# SCH_Keyboard_2024-06-21.net
KiCad netlist of a schematic drawn in EasyEDA
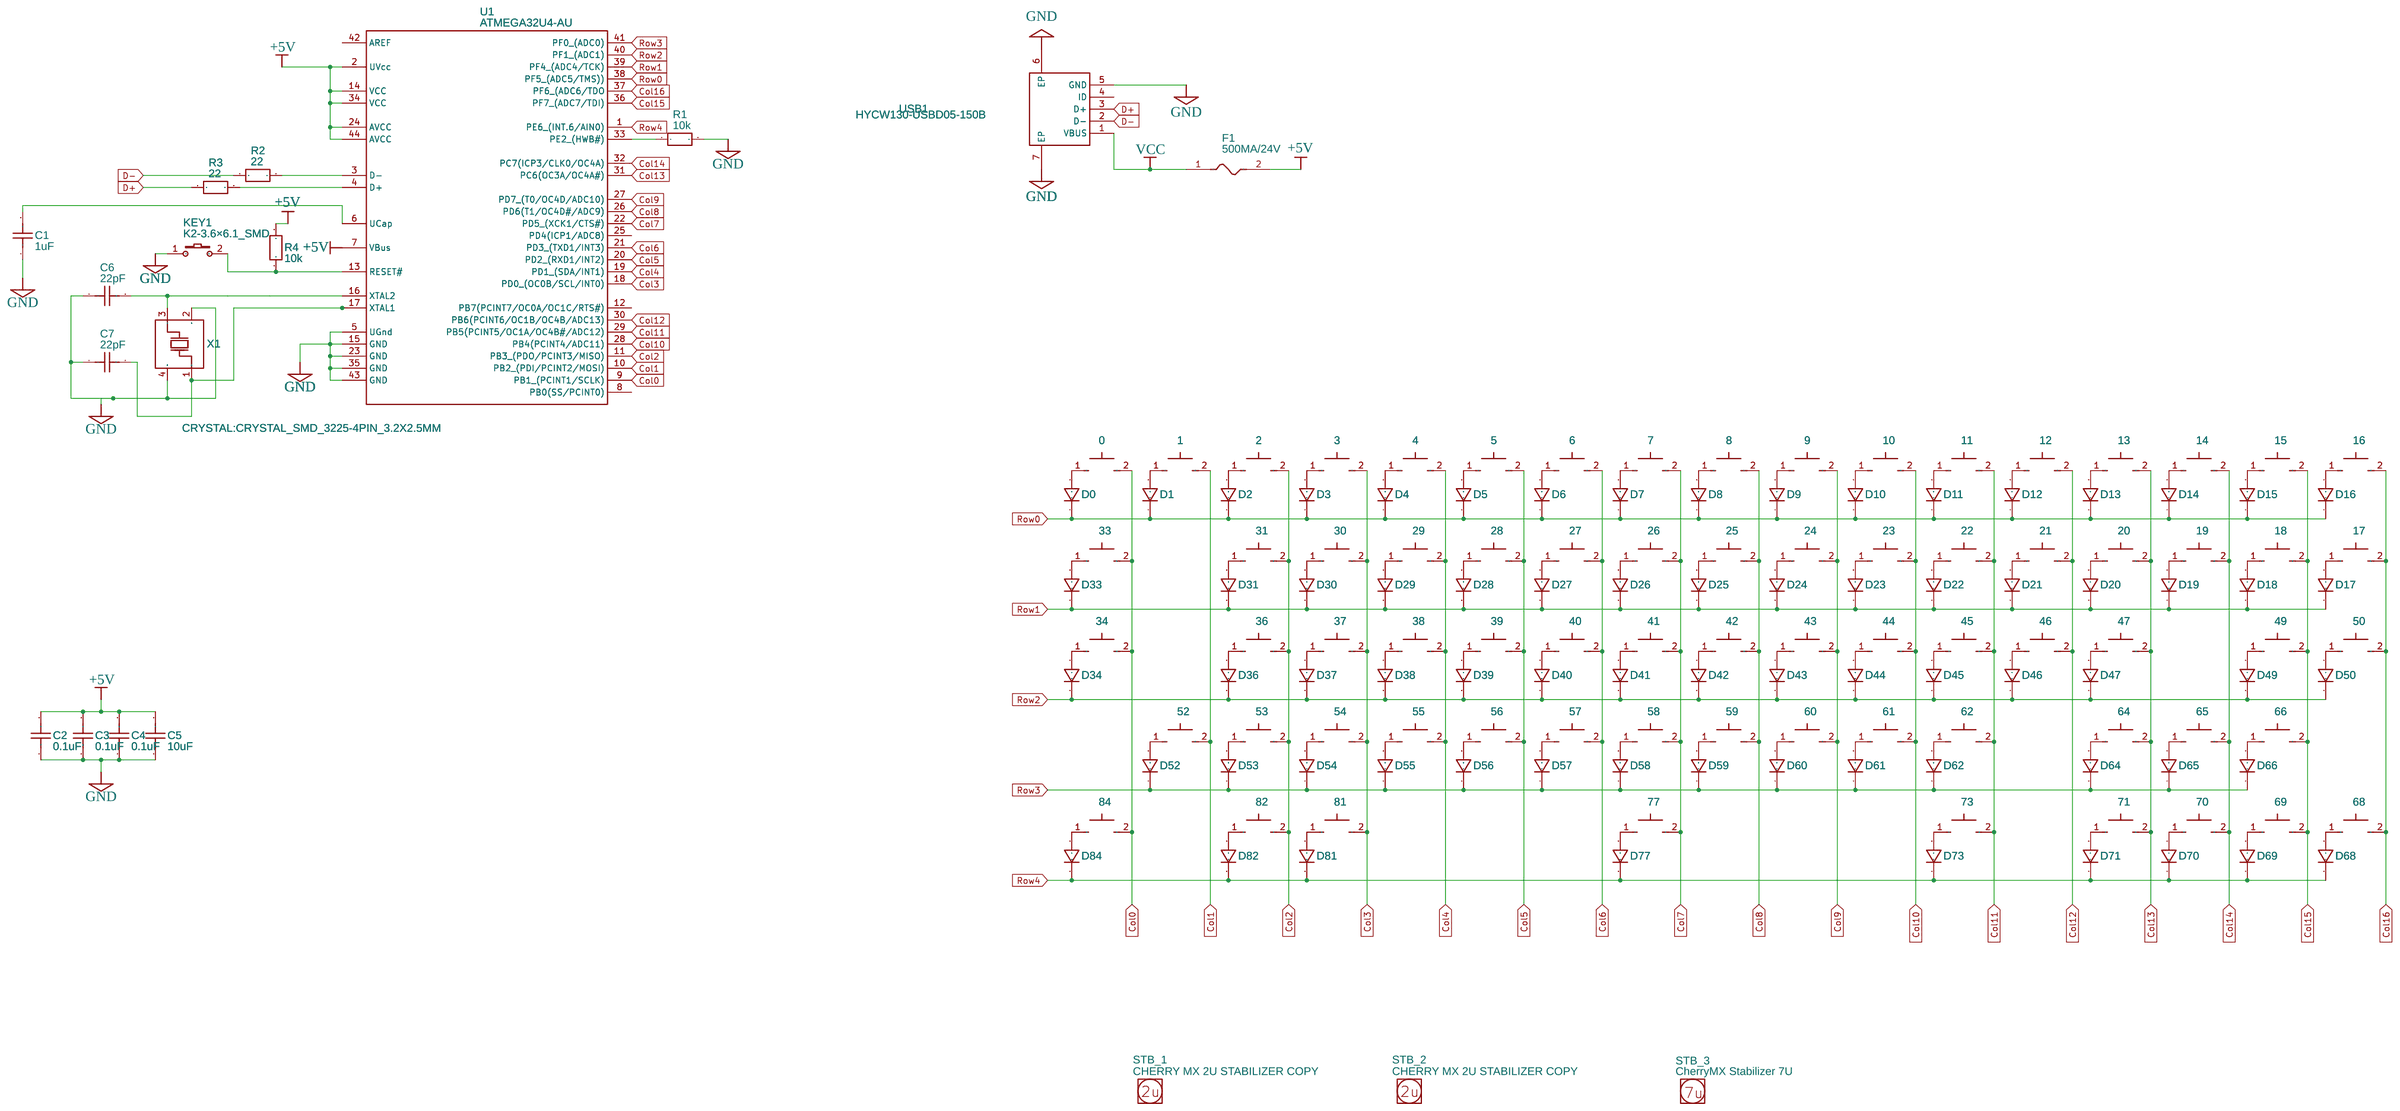
[diagram p0: schematic sheet]

(export (version "E")
  (design (tool "Eeschema 10.0.6"))
  (components
    (comp (ref "0")
      (value "CPG151101S11-16")
      (fields (field (name "Manufacturer") "Kailh(凯华)"))
      (libsource (lib "") (part "CPG151101S11-16"))
    )
    (comp (ref "1")
      (value "CPG151101S11-16")
      (fields (field (name "Manufacturer") "Kailh(凯华)"))
      (libsource (lib "") (part "CPG151101S11-16"))
    )
    (comp (ref "2")
      (value "CPG151101S11-16")
      (fields (field (name "Manufacturer") "Kailh(凯华)"))
      (libsource (lib "") (part "CPG151101S11-16"))
    )
    (comp (ref "3")
      (value "CPG151101S11-16")
      (fields (field (name "Manufacturer") "Kailh(凯华)"))
      (libsource (lib "") (part "CPG151101S11-16"))
    )
    (comp (ref "4")
      (value "CPG151101S11-16")
      (fields (field (name "Manufacturer") "Kailh(凯华)"))
      (libsource (lib "") (part "CPG151101S11-16"))
    )
    (comp (ref "5")
      (value "CPG151101S11-16")
      (fields (field (name "Manufacturer") "Kailh(凯华)"))
      (libsource (lib "") (part "CPG151101S11-16"))
    )
    (comp (ref "6")
      (value "CPG151101S11-16")
      (fields (field (name "Manufacturer") "Kailh(凯华)"))
      (libsource (lib "") (part "CPG151101S11-16"))
    )
    (comp (ref "7")
      (value "CPG151101S11-16")
      (fields (field (name "Manufacturer") "Kailh(凯华)"))
      (libsource (lib "") (part "CPG151101S11-16"))
    )
    (comp (ref "8")
      (value "CPG151101S11-16")
      (fields (field (name "Manufacturer") "Kailh(凯华)"))
      (libsource (lib "") (part "CPG151101S11-16"))
    )
    (comp (ref "9")
      (value "CPG151101S11-16")
      (fields (field (name "Manufacturer") "Kailh(凯华)"))
      (libsource (lib "") (part "CPG151101S11-16"))
    )
    (comp (ref "10")
      (value "CPG151101S11-16")
      (fields (field (name "Manufacturer") "Kailh(凯华)"))
      (libsource (lib "") (part "CPG151101S11-16"))
    )
    (comp (ref "11")
      (value "CPG151101S11-16")
      (fields (field (name "Manufacturer") "Kailh(凯华)"))
      (libsource (lib "") (part "CPG151101S11-16"))
    )
    (comp (ref "12")
      (value "CPG151101S11-16")
      (fields (field (name "Manufacturer") "Kailh(凯华)"))
      (libsource (lib "") (part "CPG151101S11-16"))
    )
    (comp (ref "13")
      (value "CPG151101S11-16")
      (fields (field (name "Manufacturer") "Kailh(凯华)"))
      (libsource (lib "") (part "CPG151101S11-16"))
    )
    (comp (ref "14")
      (value "CPG151101S11-16")
      (fields (field (name "Manufacturer") "Kailh(凯华)"))
      (libsource (lib "") (part "CPG151101S11-16"))
    )
    (comp (ref "15")
      (value "CPG151101S11-16")
      (fields (field (name "Manufacturer") "Kailh(凯华)"))
      (libsource (lib "") (part "CPG151101S11-16"))
    )
    (comp (ref "16")
      (value "CPG151101S11-16")
      (fields (field (name "Manufacturer") "Kailh(凯华)"))
      (libsource (lib "") (part "CPG151101S11-16"))
    )
    (comp (ref "17")
      (value "CPG151101S11-16")
      (fields (field (name "Manufacturer") "Kailh(凯华)"))
      (libsource (lib "") (part "CPG151101S11-16"))
    )
    (comp (ref "18")
      (value "CPG151101S11-16")
      (fields (field (name "Manufacturer") "Kailh(凯华)"))
      (libsource (lib "") (part "CPG151101S11-16"))
    )
    (comp (ref "19")
      (value "CPG151101S11-16")
      (fields (field (name "Manufacturer") "Kailh(凯华)"))
      (libsource (lib "") (part "CPG151101S11-16"))
    )
    (comp (ref "20")
      (value "CPG151101S11-16")
      (fields (field (name "Manufacturer") "Kailh(凯华)"))
      (libsource (lib "") (part "CPG151101S11-16"))
    )
    (comp (ref "21")
      (value "CPG151101S11-16")
      (fields (field (name "Manufacturer") "Kailh(凯华)"))
      (libsource (lib "") (part "CPG151101S11-16"))
    )
    (comp (ref "22")
      (value "CPG151101S11-16")
      (fields (field (name "Manufacturer") "Kailh(凯华)"))
      (libsource (lib "") (part "CPG151101S11-16"))
    )
    (comp (ref "23")
      (value "CPG151101S11-16")
      (fields (field (name "Manufacturer") "Kailh(凯华)"))
      (libsource (lib "") (part "CPG151101S11-16"))
    )
    (comp (ref "24")
      (value "CPG151101S11-16")
      (fields (field (name "Manufacturer") "Kailh(凯华)"))
      (libsource (lib "") (part "CPG151101S11-16"))
    )
    (comp (ref "25")
      (value "CPG151101S11-16")
      (fields (field (name "Manufacturer") "Kailh(凯华)"))
      (libsource (lib "") (part "CPG151101S11-16"))
    )
    (comp (ref "26")
      (value "CPG151101S11-16")
      (fields (field (name "Manufacturer") "Kailh(凯华)"))
      (libsource (lib "") (part "CPG151101S11-16"))
    )
    (comp (ref "27")
      (value "CPG151101S11-16")
      (fields (field (name "Manufacturer") "Kailh(凯华)"))
      (libsource (lib "") (part "CPG151101S11-16"))
    )
    (comp (ref "28")
      (value "CPG151101S11-16")
      (fields (field (name "Manufacturer") "Kailh(凯华)"))
      (libsource (lib "") (part "CPG151101S11-16"))
    )
    (comp (ref "29")
      (value "CPG151101S11-16")
      (fields (field (name "Manufacturer") "Kailh(凯华)"))
      (libsource (lib "") (part "CPG151101S11-16"))
    )
    (comp (ref "30")
      (value "CPG151101S11-16")
      (fields (field (name "Manufacturer") "Kailh(凯华)"))
      (libsource (lib "") (part "CPG151101S11-16"))
    )
    (comp (ref "31")
      (value "CPG151101S11-16")
      (fields (field (name "Manufacturer") "Kailh(凯华)"))
      (libsource (lib "") (part "CPG151101S11-16"))
    )
    (comp (ref "33")
      (value "CPG151101S11-16")
      (fields (field (name "Manufacturer") "Kailh(凯华)"))
      (libsource (lib "") (part "CPG151101S11-16"))
    )
    (comp (ref "34")
      (value "CPG151101S11-16")
      (fields (field (name "Manufacturer") "Kailh(凯华)"))
      (libsource (lib "") (part "CPG151101S11-16"))
    )
    (comp (ref "36")
      (value "CPG151101S11-16")
      (fields (field (name "Manufacturer") "Kailh(凯华)"))
      (libsource (lib "") (part "CPG151101S11-16"))
    )
    (comp (ref "37")
      (value "CPG151101S11-16")
      (fields (field (name "Manufacturer") "Kailh(凯华)"))
      (libsource (lib "") (part "CPG151101S11-16"))
    )
    (comp (ref "38")
      (value "CPG151101S11-16")
      (fields (field (name "Manufacturer") "Kailh(凯华)"))
      (libsource (lib "") (part "CPG151101S11-16"))
    )
    (comp (ref "39")
      (value "CPG151101S11-16")
      (fields (field (name "Manufacturer") "Kailh(凯华)"))
      (libsource (lib "") (part "CPG151101S11-16"))
    )
    (comp (ref "40")
      (value "CPG151101S11-16")
      (fields (field (name "Manufacturer") "Kailh(凯华)"))
      (libsource (lib "") (part "CPG151101S11-16"))
    )
    (comp (ref "41")
      (value "CPG151101S11-16")
      (fields (field (name "Manufacturer") "Kailh(凯华)"))
      (libsource (lib "") (part "CPG151101S11-16"))
    )
    (comp (ref "42")
      (value "CPG151101S11-16")
      (fields (field (name "Manufacturer") "Kailh(凯华)"))
      (libsource (lib "") (part "CPG151101S11-16"))
    )
    (comp (ref "43")
      (value "CPG151101S11-16")
      (fields (field (name "Manufacturer") "Kailh(凯华)"))
      (libsource (lib "") (part "CPG151101S11-16"))
    )
    (comp (ref "44")
      (value "CPG151101S11-16")
      (fields (field (name "Manufacturer") "Kailh(凯华)"))
      (libsource (lib "") (part "CPG151101S11-16"))
    )
    (comp (ref "45")
      (value "CPG151101S11-16")
      (fields (field (name "Manufacturer") "Kailh(凯华)"))
      (libsource (lib "") (part "CPG151101S11-16"))
    )
    (comp (ref "46")
      (value "CPG151101S11-16")
      (fields (field (name "Manufacturer") "Kailh(凯华)"))
      (libsource (lib "") (part "CPG151101S11-16"))
    )
    (comp (ref "47")
      (value "CPG151101S11-16")
      (fields (field (name "Manufacturer") "Kailh(凯华)"))
      (libsource (lib "") (part "CPG151101S11-16"))
    )
    (comp (ref "49")
      (value "CPG151101S11-16")
      (fields (field (name "Manufacturer") "Kailh(凯华)"))
      (libsource (lib "") (part "CPG151101S11-16"))
    )
    (comp (ref "50")
      (value "CPG151101S11-16")
      (fields (field (name "Manufacturer") "Kailh(凯华)"))
      (libsource (lib "") (part "CPG151101S11-16"))
    )
    (comp (ref "52")
      (value "CPG151101S11-16")
      (fields (field (name "Manufacturer") "Kailh(凯华)"))
      (libsource (lib "") (part "CPG151101S11-16"))
    )
    (comp (ref "53")
      (value "CPG151101S11-16")
      (fields (field (name "Manufacturer") "Kailh(凯华)"))
      (libsource (lib "") (part "CPG151101S11-16"))
    )
    (comp (ref "54")
      (value "CPG151101S11-16")
      (fields (field (name "Manufacturer") "Kailh(凯华)"))
      (libsource (lib "") (part "CPG151101S11-16"))
    )
    (comp (ref "55")
      (value "CPG151101S11-16")
      (fields (field (name "Manufacturer") "Kailh(凯华)"))
      (libsource (lib "") (part "CPG151101S11-16"))
    )
    (comp (ref "56")
      (value "CPG151101S11-16")
      (fields (field (name "Manufacturer") "Kailh(凯华)"))
      (libsource (lib "") (part "CPG151101S11-16"))
    )
    (comp (ref "57")
      (value "CPG151101S11-16")
      (fields (field (name "Manufacturer") "Kailh(凯华)"))
      (libsource (lib "") (part "CPG151101S11-16"))
    )
    (comp (ref "58")
      (value "CPG151101S11-16")
      (fields (field (name "Manufacturer") "Kailh(凯华)"))
      (libsource (lib "") (part "CPG151101S11-16"))
    )
    (comp (ref "59")
      (value "CPG151101S11-16")
      (fields (field (name "Manufacturer") "Kailh(凯华)"))
      (libsource (lib "") (part "CPG151101S11-16"))
    )
    (comp (ref "60")
      (value "CPG151101S11-16")
      (fields (field (name "Manufacturer") "Kailh(凯华)"))
      (libsource (lib "") (part "CPG151101S11-16"))
    )
    (comp (ref "61")
      (value "CPG151101S11-16")
      (fields (field (name "Manufacturer") "Kailh(凯华)"))
      (libsource (lib "") (part "CPG151101S11-16"))
    )
    (comp (ref "62")
      (value "CPG151101S11-16")
      (fields (field (name "Manufacturer") "Kailh(凯华)"))
      (libsource (lib "") (part "CPG151101S11-16"))
    )
    (comp (ref "64")
      (value "CPG151101S11-16")
      (fields (field (name "Manufacturer") "Kailh(凯华)"))
      (libsource (lib "") (part "CPG151101S11-16"))
    )
    (comp (ref "65")
      (value "CPG151101S11-16")
      (fields (field (name "Manufacturer") "Kailh(凯华)"))
      (libsource (lib "") (part "CPG151101S11-16"))
    )
    (comp (ref "66")
      (value "CPG151101S11-16")
      (fields (field (name "Manufacturer") "Kailh(凯华)"))
      (libsource (lib "") (part "CPG151101S11-16"))
    )
    (comp (ref "68")
      (value "CPG151101S11-16")
      (fields (field (name "Manufacturer") "Kailh(凯华)"))
      (libsource (lib "") (part "CPG151101S11-16"))
    )
    (comp (ref "69")
      (value "CPG151101S11-16")
      (fields (field (name "Manufacturer") "Kailh(凯华)"))
      (libsource (lib "") (part "CPG151101S11-16"))
    )
    (comp (ref "70")
      (value "CPG151101S11-16")
      (fields (field (name "Manufacturer") "Kailh(凯华)"))
      (libsource (lib "") (part "CPG151101S11-16"))
    )
    (comp (ref "71")
      (value "CPG151101S11-16")
      (fields (field (name "Manufacturer") "Kailh(凯华)"))
      (libsource (lib "") (part "CPG151101S11-16"))
    )
    (comp (ref "73")
      (value "CPG151101S11-16")
      (fields (field (name "Manufacturer") "Kailh(凯华)"))
      (libsource (lib "") (part "CPG151101S11-16"))
    )
    (comp (ref "77")
      (value "CPG151101S11-16")
      (fields (field (name "Manufacturer") "Kailh(凯华)"))
      (libsource (lib "") (part "CPG151101S11-16"))
    )
    (comp (ref "81")
      (value "CPG151101S11-16")
      (fields (field (name "Manufacturer") "Kailh(凯华)"))
      (libsource (lib "") (part "CPG151101S11-16"))
    )
    (comp (ref "82")
      (value "CPG151101S11-16")
      (fields (field (name "Manufacturer") "Kailh(凯华)"))
      (libsource (lib "") (part "CPG151101S11-16"))
    )
    (comp (ref "84")
      (value "CPG151101S11-16")
      (fields (field (name "Manufacturer") "Kailh(凯华)"))
      (libsource (lib "") (part "CPG151101S11-16"))
    )
    (comp (ref "C1") (value "1uF") (libsource (lib "") (part "C_0603_US_1")))
    (comp (ref "C2") (value "0.1uF") (libsource (lib "") (part "C_0603_US_1")))
    (comp (ref "C3") (value "0.1uF") (libsource (lib "") (part "C_0603_US_1")))
    (comp (ref "C4") (value "0.1uF") (libsource (lib "") (part "C_0603_US_1")))
    (comp (ref "C5") (value "10uF") (libsource (lib "") (part "C_0603_US_1")))
    (comp (ref "C6") (value "22pF") (libsource (lib "") (part "C_0603_US")))
    (comp (ref "C7") (value "22pF") (libsource (lib "") (part "C_0603_US")))
    (comp (ref "D0")
      (value "1N4007W")
      (fields (field (name "Manufacturer") "BLUE ROCKET"))
      (libsource (lib "") (part "1N4007W"))
    )
    (comp (ref "D1")
      (value "1N4007W")
      (fields (field (name "Manufacturer") "BLUE ROCKET"))
      (libsource (lib "") (part "1N4007W"))
    )
    (comp (ref "D2")
      (value "1N4007W")
      (fields (field (name "Manufacturer") "BLUE ROCKET"))
      (libsource (lib "") (part "1N4007W"))
    )
    (comp (ref "D3")
      (value "1N4007W")
      (fields (field (name "Manufacturer") "BLUE ROCKET"))
      (libsource (lib "") (part "1N4007W"))
    )
    (comp (ref "D4")
      (value "1N4007W")
      (fields (field (name "Manufacturer") "BLUE ROCKET"))
      (libsource (lib "") (part "1N4007W"))
    )
    (comp (ref "D5")
      (value "1N4007W")
      (fields (field (name "Manufacturer") "BLUE ROCKET"))
      (libsource (lib "") (part "1N4007W"))
    )
    (comp (ref "D6")
      (value "1N4007W")
      (fields (field (name "Manufacturer") "BLUE ROCKET"))
      (libsource (lib "") (part "1N4007W"))
    )
    (comp (ref "D7")
      (value "1N4007W")
      (fields (field (name "Manufacturer") "BLUE ROCKET"))
      (libsource (lib "") (part "1N4007W"))
    )
    (comp (ref "D8")
      (value "1N4007W")
      (fields (field (name "Manufacturer") "BLUE ROCKET"))
      (libsource (lib "") (part "1N4007W"))
    )
    (comp (ref "D9")
      (value "1N4007W")
      (fields (field (name "Manufacturer") "BLUE ROCKET"))
      (libsource (lib "") (part "1N4007W"))
    )
    (comp (ref "D10")
      (value "1N4007W")
      (fields (field (name "Manufacturer") "BLUE ROCKET"))
      (libsource (lib "") (part "1N4007W"))
    )
    (comp (ref "D11")
      (value "1N4007W")
      (fields (field (name "Manufacturer") "BLUE ROCKET"))
      (libsource (lib "") (part "1N4007W"))
    )
    (comp (ref "D12")
      (value "1N4007W")
      (fields (field (name "Manufacturer") "BLUE ROCKET"))
      (libsource (lib "") (part "1N4007W"))
    )
    (comp (ref "D13")
      (value "1N4007W")
      (fields (field (name "Manufacturer") "BLUE ROCKET"))
      (libsource (lib "") (part "1N4007W"))
    )
    (comp (ref "D14")
      (value "1N4007W")
      (fields (field (name "Manufacturer") "BLUE ROCKET"))
      (libsource (lib "") (part "1N4007W"))
    )
    (comp (ref "D15")
      (value "1N4007W")
      (fields (field (name "Manufacturer") "BLUE ROCKET"))
      (libsource (lib "") (part "1N4007W"))
    )
    (comp (ref "D16")
      (value "1N4007W")
      (fields (field (name "Manufacturer") "BLUE ROCKET"))
      (libsource (lib "") (part "1N4007W"))
    )
    (comp (ref "D17")
      (value "1N4007W")
      (fields (field (name "Manufacturer") "BLUE ROCKET"))
      (libsource (lib "") (part "1N4007W"))
    )
    (comp (ref "D18")
      (value "1N4007W")
      (fields (field (name "Manufacturer") "BLUE ROCKET"))
      (libsource (lib "") (part "1N4007W"))
    )
    (comp (ref "D19")
      (value "1N4007W")
      (fields (field (name "Manufacturer") "BLUE ROCKET"))
      (libsource (lib "") (part "1N4007W"))
    )
    (comp (ref "D20")
      (value "1N4007W")
      (fields (field (name "Manufacturer") "BLUE ROCKET"))
      (libsource (lib "") (part "1N4007W"))
    )
    (comp (ref "D21")
      (value "1N4007W")
      (fields (field (name "Manufacturer") "BLUE ROCKET"))
      (libsource (lib "") (part "1N4007W"))
    )
    (comp (ref "D22")
      (value "1N4007W")
      (fields (field (name "Manufacturer") "BLUE ROCKET"))
      (libsource (lib "") (part "1N4007W"))
    )
    (comp (ref "D23")
      (value "1N4007W")
      (fields (field (name "Manufacturer") "BLUE ROCKET"))
      (libsource (lib "") (part "1N4007W"))
    )
    (comp (ref "D24")
      (value "1N4007W")
      (fields (field (name "Manufacturer") "BLUE ROCKET"))
      (libsource (lib "") (part "1N4007W"))
    )
    (comp (ref "D25")
      (value "1N4007W")
      (fields (field (name "Manufacturer") "BLUE ROCKET"))
      (libsource (lib "") (part "1N4007W"))
    )
    (comp (ref "D26")
      (value "1N4007W")
      (fields (field (name "Manufacturer") "BLUE ROCKET"))
      (libsource (lib "") (part "1N4007W"))
    )
    (comp (ref "D27")
      (value "1N4007W")
      (fields (field (name "Manufacturer") "BLUE ROCKET"))
      (libsource (lib "") (part "1N4007W"))
    )
    (comp (ref "D28")
      (value "1N4007W")
      (fields (field (name "Manufacturer") "BLUE ROCKET"))
      (libsource (lib "") (part "1N4007W"))
    )
    (comp (ref "D29")
      (value "1N4007W")
      (fields (field (name "Manufacturer") "BLUE ROCKET"))
      (libsource (lib "") (part "1N4007W"))
    )
    (comp (ref "D30")
      (value "1N4007W")
      (fields (field (name "Manufacturer") "BLUE ROCKET"))
      (libsource (lib "") (part "1N4007W"))
    )
    (comp (ref "D31")
      (value "1N4007W")
      (fields (field (name "Manufacturer") "BLUE ROCKET"))
      (libsource (lib "") (part "1N4007W"))
    )
    (comp (ref "D33")
      (value "1N4007W")
      (fields (field (name "Manufacturer") "BLUE ROCKET"))
      (libsource (lib "") (part "1N4007W"))
    )
    (comp (ref "D34")
      (value "1N4007W")
      (fields (field (name "Manufacturer") "BLUE ROCKET"))
      (libsource (lib "") (part "1N4007W"))
    )
    (comp (ref "D36")
      (value "1N4007W")
      (fields (field (name "Manufacturer") "BLUE ROCKET"))
      (libsource (lib "") (part "1N4007W"))
    )
    (comp (ref "D37")
      (value "1N4007W")
      (fields (field (name "Manufacturer") "BLUE ROCKET"))
      (libsource (lib "") (part "1N4007W"))
    )
    (comp (ref "D38")
      (value "1N4007W")
      (fields (field (name "Manufacturer") "BLUE ROCKET"))
      (libsource (lib "") (part "1N4007W"))
    )
    (comp (ref "D39")
      (value "1N4007W")
      (fields (field (name "Manufacturer") "BLUE ROCKET"))
      (libsource (lib "") (part "1N4007W"))
    )
    (comp (ref "D40")
      (value "1N4007W")
      (fields (field (name "Manufacturer") "BLUE ROCKET"))
      (libsource (lib "") (part "1N4007W"))
    )
    (comp (ref "D41")
      (value "1N4007W")
      (fields (field (name "Manufacturer") "BLUE ROCKET"))
      (libsource (lib "") (part "1N4007W"))
    )
    (comp (ref "D42")
      (value "1N4007W")
      (fields (field (name "Manufacturer") "BLUE ROCKET"))
      (libsource (lib "") (part "1N4007W"))
    )
    (comp (ref "D43")
      (value "1N4007W")
      (fields (field (name "Manufacturer") "BLUE ROCKET"))
      (libsource (lib "") (part "1N4007W"))
    )
    (comp (ref "D44")
      (value "1N4007W")
      (fields (field (name "Manufacturer") "BLUE ROCKET"))
      (libsource (lib "") (part "1N4007W"))
    )
    (comp (ref "D45")
      (value "1N4007W")
      (fields (field (name "Manufacturer") "BLUE ROCKET"))
      (libsource (lib "") (part "1N4007W"))
    )
    (comp (ref "D46")
      (value "1N4007W")
      (fields (field (name "Manufacturer") "BLUE ROCKET"))
      (libsource (lib "") (part "1N4007W"))
    )
    (comp (ref "D47")
      (value "1N4007W")
      (fields (field (name "Manufacturer") "BLUE ROCKET"))
      (libsource (lib "") (part "1N4007W"))
    )
    (comp (ref "D49")
      (value "1N4007W")
      (fields (field (name "Manufacturer") "BLUE ROCKET"))
      (libsource (lib "") (part "1N4007W"))
    )
    (comp (ref "D50")
      (value "1N4007W")
      (fields (field (name "Manufacturer") "BLUE ROCKET"))
      (libsource (lib "") (part "1N4007W"))
    )
    (comp (ref "D52")
      (value "1N4007W")
      (fields (field (name "Manufacturer") "BLUE ROCKET"))
      (libsource (lib "") (part "1N4007W"))
    )
    (comp (ref "D53")
      (value "1N4007W")
      (fields (field (name "Manufacturer") "BLUE ROCKET"))
      (libsource (lib "") (part "1N4007W"))
    )
    (comp (ref "D54")
      (value "1N4007W")
      (fields (field (name "Manufacturer") "BLUE ROCKET"))
      (libsource (lib "") (part "1N4007W"))
    )
    (comp (ref "D55")
      (value "1N4007W")
      (fields (field (name "Manufacturer") "BLUE ROCKET"))
      (libsource (lib "") (part "1N4007W"))
    )
    (comp (ref "D56")
      (value "1N4007W")
      (fields (field (name "Manufacturer") "BLUE ROCKET"))
      (libsource (lib "") (part "1N4007W"))
    )
    (comp (ref "D57")
      (value "1N4007W")
      (fields (field (name "Manufacturer") "BLUE ROCKET"))
      (libsource (lib "") (part "1N4007W"))
    )
    (comp (ref "D58")
      (value "1N4007W")
      (fields (field (name "Manufacturer") "BLUE ROCKET"))
      (libsource (lib "") (part "1N4007W"))
    )
    (comp (ref "D59")
      (value "1N4007W")
      (fields (field (name "Manufacturer") "BLUE ROCKET"))
      (libsource (lib "") (part "1N4007W"))
    )
    (comp (ref "D60")
      (value "1N4007W")
      (fields (field (name "Manufacturer") "BLUE ROCKET"))
      (libsource (lib "") (part "1N4007W"))
    )
    (comp (ref "D61")
      (value "1N4007W")
      (fields (field (name "Manufacturer") "BLUE ROCKET"))
      (libsource (lib "") (part "1N4007W"))
    )
    (comp (ref "D62")
      (value "1N4007W")
      (fields (field (name "Manufacturer") "BLUE ROCKET"))
      (libsource (lib "") (part "1N4007W"))
    )
    (comp (ref "D64")
      (value "1N4007W")
      (fields (field (name "Manufacturer") "BLUE ROCKET"))
      (libsource (lib "") (part "1N4007W"))
    )
    (comp (ref "D65")
      (value "1N4007W")
      (fields (field (name "Manufacturer") "BLUE ROCKET"))
      (libsource (lib "") (part "1N4007W"))
    )
    (comp (ref "D66")
      (value "1N4007W")
      (fields (field (name "Manufacturer") "BLUE ROCKET"))
      (libsource (lib "") (part "1N4007W"))
    )
    (comp (ref "D68")
      (value "1N4007W")
      (fields (field (name "Manufacturer") "BLUE ROCKET"))
      (libsource (lib "") (part "1N4007W"))
    )
    (comp (ref "D69")
      (value "1N4007W")
      (fields (field (name "Manufacturer") "BLUE ROCKET"))
      (libsource (lib "") (part "1N4007W"))
    )
    (comp (ref "D70")
      (value "1N4007W")
      (fields (field (name "Manufacturer") "BLUE ROCKET"))
      (libsource (lib "") (part "1N4007W"))
    )
    (comp (ref "D71")
      (value "1N4007W")
      (fields (field (name "Manufacturer") "BLUE ROCKET"))
      (libsource (lib "") (part "1N4007W"))
    )
    (comp (ref "D73")
      (value "1N4007W")
      (fields (field (name "Manufacturer") "BLUE ROCKET"))
      (libsource (lib "") (part "1N4007W"))
    )
    (comp (ref "D77")
      (value "1N4007W")
      (fields (field (name "Manufacturer") "BLUE ROCKET"))
      (libsource (lib "") (part "1N4007W"))
    )
    (comp (ref "D81")
      (value "1N4007W")
      (fields (field (name "Manufacturer") "BLUE ROCKET"))
      (libsource (lib "") (part "1N4007W"))
    )
    (comp (ref "D82")
      (value "1N4007W")
      (fields (field (name "Manufacturer") "BLUE ROCKET"))
      (libsource (lib "") (part "1N4007W"))
    )
    (comp (ref "D84")
      (value "1N4007W")
      (fields (field (name "Manufacturer") "BLUE ROCKET"))
      (libsource (lib "") (part "1N4007W"))
    )
    (comp (ref "F1")
      (value "500MA/24V")
      (fields (field (name "Manufacturer Part") "500mA/24V") (field (name "Manufacturer") "DOWO(东沃)"))
      (libsource (lib "") (part "500MA/24V"))
    )
    (comp (ref "KEY1")
      (value "K2-3.6×6.1_SMD")
      (fields (field (name "Manufacturer Part") "K2-1107ST-A4SW-06"))
      (libsource (lib "") (part "K2-3.6×6.1_SMD"))
    )
    (comp (ref "R1") (value "10k") (libsource (lib "") (part "R_0603_EU")))
    (comp (ref "R2") (value "22") (libsource (lib "") (part "R_0603_EU")))
    (comp (ref "R3") (value "22") (libsource (lib "") (part "R_0603_EU")))
    (comp (ref "R4") (value "10k") (libsource (lib "") (part "R_0603_EU_1")))
    (comp (ref "STB_1")
      (value "CHERRY MX 2U STABILIZER COPY")
      (fields (field (name "Manufacturer Part") "G99-0742"))
      (libsource (lib "") (part "CHERRY MX 2U STABILIZER COPY"))
    )
    (comp (ref "STB_2")
      (value "CHERRY MX 2U STABILIZER COPY")
      (fields (field (name "Manufacturer Part") "G99-0742"))
      (libsource (lib "") (part "CHERRY MX 2U STABILIZER COPY"))
    )
    (comp (ref "STB_3")
      (value "CherryMX Stabilizer 7U")
      (fields (field (name "Manufacturer Part") "G99-0379"))
      (libsource (lib "") (part "CherryMX Stabilizer 7U"))
    )
    (comp (ref "U1")
      (value "ATMEGA32U4-AU")
      (fields (field (name "Manufacturer") "MICROCHIP(美国微芯)"))
      (libsource (lib "") (part "ATMEGA32U4-AU"))
    )
    (comp (ref "USB1")
      (value "HYCW130-USBD05-150B")
      (fields (field (name "Manufacturer") "华宇创"))
      (libsource (lib "") (part "HYCW130-USBD05-150B"))
    )
    (comp (ref "X1")
      (value "CRYSTAL:CRYSTAL_SMD_3225-4PIN_3.2X2.5MM")
      (fields (field (name "Manufacturer Part") "Crystal:Crystal_SMD_3225-4Pin_3.2x2.5mm"))
      (libsource (lib "") (part "CRYSTAL{colon}CRYSTAL_SMD_3225-4PIN_3.2X2.5MM"))
    )
  )
  (nets
    (net (code "1") (name "+5V") (class "Default")
      (node (ref "C2") (pin "2") (pinfunction "2_2") (pintype "unspecified"))
      (node (ref "C3") (pin "2") (pinfunction "2_2") (pintype "unspecified"))
      (node (ref "C4") (pin "2") (pinfunction "2_2") (pintype "unspecified"))
      (node (ref "C5") (pin "2") (pinfunction "2_2") (pintype "unspecified"))
      (node (ref "F1") (pin "2") (pinfunction "2_2") (pintype "unspecified"))
      (node (ref "R4") (pin "2") (pinfunction "2_2") (pintype "unspecified"))
      (node (ref "U1") (pin "14") (pinfunction "VCC_14") (pintype "passive"))
      (node (ref "U1") (pin "2") (pinfunction "UVcc_2") (pintype "passive"))
      (node (ref "U1") (pin "24") (pinfunction "AVCC_24") (pintype "passive"))
      (node (ref "U1") (pin "34") (pinfunction "VCC_34") (pintype "passive"))
      (node (ref "U1") (pin "44") (pinfunction "AVCC_44") (pintype "passive"))
      (node (ref "U1") (pin "7") (pinfunction "VBus_7") (pintype "unspecified"))
    )
    (net (code "2") (name "Col0") (class "Default")
      (node (ref "0") (pin "2") (pinfunction "2_2") (pintype "input"))
      (node (ref "33") (pin "2") (pinfunction "2_2") (pintype "input"))
      (node (ref "34") (pin "2") (pinfunction "2_2") (pintype "input"))
      (node (ref "84") (pin "2") (pinfunction "2_2") (pintype "input"))
      (node (ref "U1") (pin "9") (pinfunction "PB1_(PCINT1/SCLK)_9") (pintype "bidirectional"))
    )
    (net (code "3") (name "Col1") (class "Default")
      (node (ref "1") (pin "2") (pinfunction "2_2") (pintype "input"))
      (node (ref "52") (pin "2") (pinfunction "2_2") (pintype "input"))
      (node (ref "U1") (pin "10") (pinfunction "PB2_(PDI/PCINT2/MOSI)_10") (pintype "bidirectional"))
    )
    (net (code "4") (name "Col2") (class "Default")
      (node (ref "2") (pin "2") (pinfunction "2_2") (pintype "input"))
      (node (ref "31") (pin "2") (pinfunction "2_2") (pintype "input"))
      (node (ref "36") (pin "2") (pinfunction "2_2") (pintype "input"))
      (node (ref "53") (pin "2") (pinfunction "2_2") (pintype "input"))
      (node (ref "82") (pin "2") (pinfunction "2_2") (pintype "input"))
      (node (ref "U1") (pin "11") (pinfunction "PB3_(PDO/PCINT3/MISO)_11") (pintype "bidirectional"))
    )
    (net (code "5") (name "Col3") (class "Default")
      (node (ref "3") (pin "2") (pinfunction "2_2") (pintype "input"))
      (node (ref "30") (pin "2") (pinfunction "2_2") (pintype "input"))
      (node (ref "37") (pin "2") (pinfunction "2_2") (pintype "input"))
      (node (ref "54") (pin "2") (pinfunction "2_2") (pintype "input"))
      (node (ref "81") (pin "2") (pinfunction "2_2") (pintype "input"))
      (node (ref "U1") (pin "18") (pinfunction "PD0_(OC0B/SCL/INT0)_18") (pintype "bidirectional"))
    )
    (net (code "6") (name "Col4") (class "Default")
      (node (ref "29") (pin "2") (pinfunction "2_2") (pintype "input"))
      (node (ref "38") (pin "2") (pinfunction "2_2") (pintype "input"))
      (node (ref "4") (pin "2") (pinfunction "2_2") (pintype "input"))
      (node (ref "55") (pin "2") (pinfunction "2_2") (pintype "input"))
      (node (ref "U1") (pin "19") (pinfunction "PD1_(SDA/INT1)_19") (pintype "bidirectional"))
    )
    (net (code "7") (name "Col5") (class "Default")
      (node (ref "28") (pin "2") (pinfunction "2_2") (pintype "input"))
      (node (ref "39") (pin "2") (pinfunction "2_2") (pintype "input"))
      (node (ref "5") (pin "2") (pinfunction "2_2") (pintype "input"))
      (node (ref "56") (pin "2") (pinfunction "2_2") (pintype "input"))
      (node (ref "U1") (pin "20") (pinfunction "PD2_(RXD1/INT2)_20") (pintype "bidirectional"))
    )
    (net (code "8") (name "Col6") (class "Default")
      (node (ref "27") (pin "2") (pinfunction "2_2") (pintype "input"))
      (node (ref "40") (pin "2") (pinfunction "2_2") (pintype "input"))
      (node (ref "57") (pin "2") (pinfunction "2_2") (pintype "input"))
      (node (ref "6") (pin "2") (pinfunction "2_2") (pintype "input"))
      (node (ref "U1") (pin "21") (pinfunction "PD3_(TXD1/INT3)_21") (pintype "bidirectional"))
    )
    (net (code "9") (name "Col7") (class "Default")
      (node (ref "26") (pin "2") (pinfunction "2_2") (pintype "input"))
      (node (ref "41") (pin "2") (pinfunction "2_2") (pintype "input"))
      (node (ref "58") (pin "2") (pinfunction "2_2") (pintype "input"))
      (node (ref "7") (pin "2") (pinfunction "2_2") (pintype "input"))
      (node (ref "77") (pin "2") (pinfunction "2_2") (pintype "input"))
      (node (ref "U1") (pin "22") (pinfunction "PD5_(XCK1/CTS#)_22") (pintype "bidirectional"))
    )
    (net (code "10") (name "Col8") (class "Default")
      (node (ref "25") (pin "2") (pinfunction "2_2") (pintype "input"))
      (node (ref "42") (pin "2") (pinfunction "2_2") (pintype "input"))
      (node (ref "59") (pin "2") (pinfunction "2_2") (pintype "input"))
      (node (ref "8") (pin "2") (pinfunction "2_2") (pintype "input"))
      (node (ref "U1") (pin "26") (pinfunction "PD6(T1/OC4D#/ADC9)_26") (pintype "bidirectional"))
    )
    (net (code "11") (name "Col9") (class "Default")
      (node (ref "24") (pin "2") (pinfunction "2_2") (pintype "input"))
      (node (ref "43") (pin "2") (pinfunction "2_2") (pintype "input"))
      (node (ref "60") (pin "2") (pinfunction "2_2") (pintype "input"))
      (node (ref "9") (pin "2") (pinfunction "2_2") (pintype "input"))
      (node (ref "U1") (pin "27") (pinfunction "PD7_(T0/OC4D/ADC10)_27") (pintype "bidirectional"))
    )
    (net (code "12") (name "Col10") (class "Default")
      (node (ref "10") (pin "2") (pinfunction "2_2") (pintype "input"))
      (node (ref "23") (pin "2") (pinfunction "2_2") (pintype "input"))
      (node (ref "44") (pin "2") (pinfunction "2_2") (pintype "input"))
      (node (ref "61") (pin "2") (pinfunction "2_2") (pintype "input"))
      (node (ref "U1") (pin "28") (pinfunction "PB4(PCINT4/ADC11)_28") (pintype "bidirectional"))
    )
    (net (code "13") (name "Col11") (class "Default")
      (node (ref "11") (pin "2") (pinfunction "2_2") (pintype "input"))
      (node (ref "22") (pin "2") (pinfunction "2_2") (pintype "input"))
      (node (ref "45") (pin "2") (pinfunction "2_2") (pintype "input"))
      (node (ref "62") (pin "2") (pinfunction "2_2") (pintype "input"))
      (node (ref "73") (pin "2") (pinfunction "2_2") (pintype "input"))
      (node (ref "U1") (pin "29") (pinfunction "PB5(PCINT5/OC1A/OC4B#/ADC12)_29") (pintype "bidirectional"))
    )
    (net (code "14") (name "Col12") (class "Default")
      (node (ref "12") (pin "2") (pinfunction "2_2") (pintype "input"))
      (node (ref "21") (pin "2") (pinfunction "2_2") (pintype "input"))
      (node (ref "46") (pin "2") (pinfunction "2_2") (pintype "input"))
      (node (ref "U1") (pin "30") (pinfunction "PB6(PCINT6/OC1B/OC4B/ADC13)_30") (pintype "bidirectional"))
    )
    (net (code "15") (name "Col13") (class "Default")
      (node (ref "13") (pin "2") (pinfunction "2_2") (pintype "input"))
      (node (ref "20") (pin "2") (pinfunction "2_2") (pintype "input"))
      (node (ref "47") (pin "2") (pinfunction "2_2") (pintype "input"))
      (node (ref "64") (pin "2") (pinfunction "2_2") (pintype "input"))
      (node (ref "71") (pin "2") (pinfunction "2_2") (pintype "input"))
      (node (ref "U1") (pin "31") (pinfunction "PC6(OC3A/OC4A#)_31") (pintype "bidirectional"))
    )
    (net (code "16") (name "Col14") (class "Default")
      (node (ref "14") (pin "2") (pinfunction "2_2") (pintype "input"))
      (node (ref "19") (pin "2") (pinfunction "2_2") (pintype "input"))
      (node (ref "65") (pin "2") (pinfunction "2_2") (pintype "input"))
      (node (ref "70") (pin "2") (pinfunction "2_2") (pintype "input"))
      (node (ref "U1") (pin "32") (pinfunction "PC7(ICP3/CLK0/OC4A)_32") (pintype "bidirectional"))
    )
    (net (code "17") (name "Col15") (class "Default")
      (node (ref "15") (pin "2") (pinfunction "2_2") (pintype "input"))
      (node (ref "18") (pin "2") (pinfunction "2_2") (pintype "input"))
      (node (ref "49") (pin "2") (pinfunction "2_2") (pintype "input"))
      (node (ref "66") (pin "2") (pinfunction "2_2") (pintype "input"))
      (node (ref "69") (pin "2") (pinfunction "2_2") (pintype "input"))
      (node (ref "U1") (pin "36") (pinfunction "PF7_(ADC7/TDI)_36") (pintype "bidirectional"))
    )
    (net (code "18") (name "Col16") (class "Default")
      (node (ref "16") (pin "2") (pinfunction "2_2") (pintype "input"))
      (node (ref "17") (pin "2") (pinfunction "2_2") (pintype "input"))
      (node (ref "50") (pin "2") (pinfunction "2_2") (pintype "input"))
      (node (ref "68") (pin "2") (pinfunction "2_2") (pintype "input"))
      (node (ref "U1") (pin "37") (pinfunction "PF6_(ADC6/TDO_37") (pintype "bidirectional"))
    )
    (net (code "19") (name "D+") (class "Default")
      (node (ref "R3") (pin "1") (pinfunction "1_1") (pintype "unspecified"))
      (node (ref "USB1") (pin "3") (pinfunction "D+_3") (pintype "unspecified"))
    )
    (net (code "20") (name "D-") (class "Default")
      (node (ref "R2") (pin "1") (pinfunction "1_1") (pintype "unspecified"))
      (node (ref "USB1") (pin "2") (pinfunction "D-_2") (pintype "unspecified"))
    )
    (net (code "21") (name "GND") (class "Default")
      (node (ref "C1") (pin "1") (pinfunction "1_1") (pintype "unspecified"))
      (node (ref "C2") (pin "1") (pinfunction "1_1") (pintype "unspecified"))
      (node (ref "C3") (pin "1") (pinfunction "1_1") (pintype "unspecified"))
      (node (ref "C4") (pin "1") (pinfunction "1_1") (pintype "unspecified"))
      (node (ref "C5") (pin "1") (pinfunction "1_1") (pintype "unspecified"))
      (node (ref "C6") (pin "1") (pinfunction "1_1") (pintype "unspecified"))
      (node (ref "C7") (pin "1") (pinfunction "1_1") (pintype "unspecified"))
      (node (ref "KEY1") (pin "1") (pinfunction "1_1") (pintype "unspecified"))
      (node (ref "R1") (pin "2") (pinfunction "2_2") (pintype "unspecified"))
      (node (ref "U1") (pin "15") (pinfunction "GND_15") (pintype "passive"))
      (node (ref "U1") (pin "23") (pinfunction "GND_23") (pintype "passive"))
      (node (ref "U1") (pin "35") (pinfunction "GND_35") (pintype "passive"))
      (node (ref "U1") (pin "43") (pinfunction "GND_43") (pintype "passive"))
      (node (ref "U1") (pin "5") (pinfunction "UGnd_5") (pintype "passive"))
      (node (ref "USB1") (pin "5") (pinfunction "GND_5") (pintype "unspecified"))
      (node (ref "USB1") (pin "6") (pinfunction "EP_6") (pintype "unspecified"))
      (node (ref "USB1") (pin "7") (pinfunction "EP_7") (pintype "unspecified"))
      (node (ref "X1") (pin "2") (pinfunction "GND_2") (pintype "unspecified"))
      (node (ref "X1") (pin "4") (pinfunction "GND_4") (pintype "unspecified"))
    )
    (net (code "22") (name "Net-(0-Pad1)") (class "Default")
      (node (ref "0") (pin "1") (pinfunction "1_1") (pintype "input"))
      (node (ref "D0") (pin "2") (pinfunction "2_2") (pintype "unspecified"))
    )
    (net (code "23") (name "Net-(1-Pad1)") (class "Default")
      (node (ref "1") (pin "1") (pinfunction "1_1") (pintype "input"))
      (node (ref "D1") (pin "2") (pinfunction "2_2") (pintype "unspecified"))
    )
    (net (code "24") (name "Net-(2-Pad1)") (class "Default")
      (node (ref "2") (pin "1") (pinfunction "1_1") (pintype "input"))
      (node (ref "D2") (pin "2") (pinfunction "2_2") (pintype "unspecified"))
    )
    (net (code "25") (name "Net-(3-Pad1)") (class "Default")
      (node (ref "3") (pin "1") (pinfunction "1_1") (pintype "input"))
      (node (ref "D3") (pin "2") (pinfunction "2_2") (pintype "unspecified"))
    )
    (net (code "26") (name "Net-(4-Pad1)") (class "Default")
      (node (ref "4") (pin "1") (pinfunction "1_1") (pintype "input"))
      (node (ref "D4") (pin "2") (pinfunction "2_2") (pintype "unspecified"))
    )
    (net (code "27") (name "Net-(5-Pad1)") (class "Default")
      (node (ref "5") (pin "1") (pinfunction "1_1") (pintype "input"))
      (node (ref "D5") (pin "2") (pinfunction "2_2") (pintype "unspecified"))
    )
    (net (code "28") (name "Net-(6-Pad1)") (class "Default")
      (node (ref "6") (pin "1") (pinfunction "1_1") (pintype "input"))
      (node (ref "D6") (pin "2") (pinfunction "2_2") (pintype "unspecified"))
    )
    (net (code "29") (name "Net-(7-Pad1)") (class "Default")
      (node (ref "7") (pin "1") (pinfunction "1_1") (pintype "input"))
      (node (ref "D7") (pin "2") (pinfunction "2_2") (pintype "unspecified"))
    )
    (net (code "30") (name "Net-(8-Pad1)") (class "Default")
      (node (ref "8") (pin "1") (pinfunction "1_1") (pintype "input"))
      (node (ref "D8") (pin "2") (pinfunction "2_2") (pintype "unspecified"))
    )
    (net (code "31") (name "Net-(9-Pad1)") (class "Default")
      (node (ref "9") (pin "1") (pinfunction "1_1") (pintype "input"))
      (node (ref "D9") (pin "2") (pinfunction "2_2") (pintype "unspecified"))
    )
    (net (code "32") (name "Net-(10-Pad1)") (class "Default")
      (node (ref "10") (pin "1") (pinfunction "1_1") (pintype "input"))
      (node (ref "D10") (pin "2") (pinfunction "2_2") (pintype "unspecified"))
    )
    (net (code "33") (name "Net-(11-Pad1)") (class "Default")
      (node (ref "11") (pin "1") (pinfunction "1_1") (pintype "input"))
      (node (ref "D11") (pin "2") (pinfunction "2_2") (pintype "unspecified"))
    )
    (net (code "34") (name "Net-(12-Pad1)") (class "Default")
      (node (ref "12") (pin "1") (pinfunction "1_1") (pintype "input"))
      (node (ref "D12") (pin "2") (pinfunction "2_2") (pintype "unspecified"))
    )
    (net (code "35") (name "Net-(13-Pad1)") (class "Default")
      (node (ref "13") (pin "1") (pinfunction "1_1") (pintype "input"))
      (node (ref "D13") (pin "2") (pinfunction "2_2") (pintype "unspecified"))
    )
    (net (code "36") (name "Net-(14-Pad1)") (class "Default")
      (node (ref "14") (pin "1") (pinfunction "1_1") (pintype "input"))
      (node (ref "D14") (pin "2") (pinfunction "2_2") (pintype "unspecified"))
    )
    (net (code "37") (name "Net-(15-Pad1)") (class "Default")
      (node (ref "15") (pin "1") (pinfunction "1_1") (pintype "input"))
      (node (ref "D15") (pin "2") (pinfunction "2_2") (pintype "unspecified"))
    )
    (net (code "38") (name "Net-(16-Pad1)") (class "Default")
      (node (ref "16") (pin "1") (pinfunction "1_1") (pintype "input"))
      (node (ref "D16") (pin "2") (pinfunction "2_2") (pintype "unspecified"))
    )
    (net (code "39") (name "Net-(17-Pad1)") (class "Default")
      (node (ref "17") (pin "1") (pinfunction "1_1") (pintype "input"))
      (node (ref "D17") (pin "2") (pinfunction "2_2") (pintype "unspecified"))
    )
    (net (code "40") (name "Net-(18-Pad1)") (class "Default")
      (node (ref "18") (pin "1") (pinfunction "1_1") (pintype "input"))
      (node (ref "D18") (pin "2") (pinfunction "2_2") (pintype "unspecified"))
    )
    (net (code "41") (name "Net-(19-Pad1)") (class "Default")
      (node (ref "19") (pin "1") (pinfunction "1_1") (pintype "input"))
      (node (ref "D19") (pin "2") (pinfunction "2_2") (pintype "unspecified"))
    )
    (net (code "42") (name "Net-(20-Pad1)") (class "Default")
      (node (ref "20") (pin "1") (pinfunction "1_1") (pintype "input"))
      (node (ref "D20") (pin "2") (pinfunction "2_2") (pintype "unspecified"))
    )
    (net (code "43") (name "Net-(21-Pad1)") (class "Default")
      (node (ref "21") (pin "1") (pinfunction "1_1") (pintype "input"))
      (node (ref "D21") (pin "2") (pinfunction "2_2") (pintype "unspecified"))
    )
    (net (code "44") (name "Net-(22-Pad1)") (class "Default")
      (node (ref "22") (pin "1") (pinfunction "1_1") (pintype "input"))
      (node (ref "D22") (pin "2") (pinfunction "2_2") (pintype "unspecified"))
    )
    (net (code "45") (name "Net-(23-Pad1)") (class "Default")
      (node (ref "23") (pin "1") (pinfunction "1_1") (pintype "input"))
      (node (ref "D23") (pin "2") (pinfunction "2_2") (pintype "unspecified"))
    )
    (net (code "46") (name "Net-(24-Pad1)") (class "Default")
      (node (ref "24") (pin "1") (pinfunction "1_1") (pintype "input"))
      (node (ref "D24") (pin "2") (pinfunction "2_2") (pintype "unspecified"))
    )
    (net (code "47") (name "Net-(25-Pad1)") (class "Default")
      (node (ref "25") (pin "1") (pinfunction "1_1") (pintype "input"))
      (node (ref "D25") (pin "2") (pinfunction "2_2") (pintype "unspecified"))
    )
    (net (code "48") (name "Net-(26-Pad1)") (class "Default")
      (node (ref "26") (pin "1") (pinfunction "1_1") (pintype "input"))
      (node (ref "D26") (pin "2") (pinfunction "2_2") (pintype "unspecified"))
    )
    (net (code "49") (name "Net-(27-Pad1)") (class "Default")
      (node (ref "27") (pin "1") (pinfunction "1_1") (pintype "input"))
      (node (ref "D27") (pin "2") (pinfunction "2_2") (pintype "unspecified"))
    )
    (net (code "50") (name "Net-(28-Pad1)") (class "Default")
      (node (ref "28") (pin "1") (pinfunction "1_1") (pintype "input"))
      (node (ref "D28") (pin "2") (pinfunction "2_2") (pintype "unspecified"))
    )
    (net (code "51") (name "Net-(29-Pad1)") (class "Default")
      (node (ref "29") (pin "1") (pinfunction "1_1") (pintype "input"))
      (node (ref "D29") (pin "2") (pinfunction "2_2") (pintype "unspecified"))
    )
    (net (code "52") (name "Net-(30-Pad1)") (class "Default")
      (node (ref "30") (pin "1") (pinfunction "1_1") (pintype "input"))
      (node (ref "D30") (pin "2") (pinfunction "2_2") (pintype "unspecified"))
    )
    (net (code "53") (name "Net-(31-Pad1)") (class "Default")
      (node (ref "31") (pin "1") (pinfunction "1_1") (pintype "input"))
      (node (ref "D31") (pin "2") (pinfunction "2_2") (pintype "unspecified"))
    )
    (net (code "54") (name "Net-(33-Pad1)") (class "Default")
      (node (ref "33") (pin "1") (pinfunction "1_1") (pintype "input"))
      (node (ref "D33") (pin "2") (pinfunction "2_2") (pintype "unspecified"))
    )
    (net (code "55") (name "Net-(34-Pad1)") (class "Default")
      (node (ref "34") (pin "1") (pinfunction "1_1") (pintype "input"))
      (node (ref "D34") (pin "2") (pinfunction "2_2") (pintype "unspecified"))
    )
    (net (code "56") (name "Net-(36-Pad1)") (class "Default")
      (node (ref "36") (pin "1") (pinfunction "1_1") (pintype "input"))
      (node (ref "D36") (pin "2") (pinfunction "2_2") (pintype "unspecified"))
    )
    (net (code "57") (name "Net-(37-Pad1)") (class "Default")
      (node (ref "37") (pin "1") (pinfunction "1_1") (pintype "input"))
      (node (ref "D37") (pin "2") (pinfunction "2_2") (pintype "unspecified"))
    )
    (net (code "58") (name "Net-(38-Pad1)") (class "Default")
      (node (ref "38") (pin "1") (pinfunction "1_1") (pintype "input"))
      (node (ref "D38") (pin "2") (pinfunction "2_2") (pintype "unspecified"))
    )
    (net (code "59") (name "Net-(39-Pad1)") (class "Default")
      (node (ref "39") (pin "1") (pinfunction "1_1") (pintype "input"))
      (node (ref "D39") (pin "2") (pinfunction "2_2") (pintype "unspecified"))
    )
    (net (code "60") (name "Net-(40-Pad1)") (class "Default")
      (node (ref "40") (pin "1") (pinfunction "1_1") (pintype "input"))
      (node (ref "D40") (pin "2") (pinfunction "2_2") (pintype "unspecified"))
    )
    (net (code "61") (name "Net-(41-Pad1)") (class "Default")
      (node (ref "41") (pin "1") (pinfunction "1_1") (pintype "input"))
      (node (ref "D41") (pin "2") (pinfunction "2_2") (pintype "unspecified"))
    )
    (net (code "62") (name "Net-(42-Pad1)") (class "Default")
      (node (ref "42") (pin "1") (pinfunction "1_1") (pintype "input"))
      (node (ref "D42") (pin "2") (pinfunction "2_2") (pintype "unspecified"))
    )
    (net (code "63") (name "Net-(43-Pad1)") (class "Default")
      (node (ref "43") (pin "1") (pinfunction "1_1") (pintype "input"))
      (node (ref "D43") (pin "2") (pinfunction "2_2") (pintype "unspecified"))
    )
    (net (code "64") (name "Net-(44-Pad1)") (class "Default")
      (node (ref "44") (pin "1") (pinfunction "1_1") (pintype "input"))
      (node (ref "D44") (pin "2") (pinfunction "2_2") (pintype "unspecified"))
    )
    (net (code "65") (name "Net-(45-Pad1)") (class "Default")
      (node (ref "45") (pin "1") (pinfunction "1_1") (pintype "input"))
      (node (ref "D45") (pin "2") (pinfunction "2_2") (pintype "unspecified"))
    )
    (net (code "66") (name "Net-(46-Pad1)") (class "Default")
      (node (ref "46") (pin "1") (pinfunction "1_1") (pintype "input"))
      (node (ref "D46") (pin "2") (pinfunction "2_2") (pintype "unspecified"))
    )
    (net (code "67") (name "Net-(47-Pad1)") (class "Default")
      (node (ref "47") (pin "1") (pinfunction "1_1") (pintype "input"))
      (node (ref "D47") (pin "2") (pinfunction "2_2") (pintype "unspecified"))
    )
    (net (code "68") (name "Net-(49-Pad1)") (class "Default")
      (node (ref "49") (pin "1") (pinfunction "1_1") (pintype "input"))
      (node (ref "D49") (pin "2") (pinfunction "2_2") (pintype "unspecified"))
    )
    (net (code "69") (name "Net-(50-Pad1)") (class "Default")
      (node (ref "50") (pin "1") (pinfunction "1_1") (pintype "input"))
      (node (ref "D50") (pin "2") (pinfunction "2_2") (pintype "unspecified"))
    )
    (net (code "70") (name "Net-(52-Pad1)") (class "Default")
      (node (ref "52") (pin "1") (pinfunction "1_1") (pintype "input"))
      (node (ref "D52") (pin "2") (pinfunction "2_2") (pintype "unspecified"))
    )
    (net (code "71") (name "Net-(53-Pad1)") (class "Default")
      (node (ref "53") (pin "1") (pinfunction "1_1") (pintype "input"))
      (node (ref "D53") (pin "2") (pinfunction "2_2") (pintype "unspecified"))
    )
    (net (code "72") (name "Net-(54-Pad1)") (class "Default")
      (node (ref "54") (pin "1") (pinfunction "1_1") (pintype "input"))
      (node (ref "D54") (pin "2") (pinfunction "2_2") (pintype "unspecified"))
    )
    (net (code "73") (name "Net-(55-Pad1)") (class "Default")
      (node (ref "55") (pin "1") (pinfunction "1_1") (pintype "input"))
      (node (ref "D55") (pin "2") (pinfunction "2_2") (pintype "unspecified"))
    )
    (net (code "74") (name "Net-(56-Pad1)") (class "Default")
      (node (ref "56") (pin "1") (pinfunction "1_1") (pintype "input"))
      (node (ref "D56") (pin "2") (pinfunction "2_2") (pintype "unspecified"))
    )
    (net (code "75") (name "Net-(57-Pad1)") (class "Default")
      (node (ref "57") (pin "1") (pinfunction "1_1") (pintype "input"))
      (node (ref "D57") (pin "2") (pinfunction "2_2") (pintype "unspecified"))
    )
    (net (code "76") (name "Net-(58-Pad1)") (class "Default")
      (node (ref "58") (pin "1") (pinfunction "1_1") (pintype "input"))
      (node (ref "D58") (pin "2") (pinfunction "2_2") (pintype "unspecified"))
    )
    (net (code "77") (name "Net-(59-Pad1)") (class "Default")
      (node (ref "59") (pin "1") (pinfunction "1_1") (pintype "input"))
      (node (ref "D59") (pin "2") (pinfunction "2_2") (pintype "unspecified"))
    )
    (net (code "78") (name "Net-(60-Pad1)") (class "Default")
      (node (ref "60") (pin "1") (pinfunction "1_1") (pintype "input"))
      (node (ref "D60") (pin "2") (pinfunction "2_2") (pintype "unspecified"))
    )
    (net (code "79") (name "Net-(61-Pad1)") (class "Default")
      (node (ref "61") (pin "1") (pinfunction "1_1") (pintype "input"))
      (node (ref "D61") (pin "2") (pinfunction "2_2") (pintype "unspecified"))
    )
    (net (code "80") (name "Net-(62-Pad1)") (class "Default")
      (node (ref "62") (pin "1") (pinfunction "1_1") (pintype "input"))
      (node (ref "D62") (pin "2") (pinfunction "2_2") (pintype "unspecified"))
    )
    (net (code "81") (name "Net-(64-Pad1)") (class "Default")
      (node (ref "64") (pin "1") (pinfunction "1_1") (pintype "input"))
      (node (ref "D64") (pin "2") (pinfunction "2_2") (pintype "unspecified"))
    )
    (net (code "82") (name "Net-(65-Pad1)") (class "Default")
      (node (ref "65") (pin "1") (pinfunction "1_1") (pintype "input"))
      (node (ref "D65") (pin "2") (pinfunction "2_2") (pintype "unspecified"))
    )
    (net (code "83") (name "Net-(66-Pad1)") (class "Default")
      (node (ref "66") (pin "1") (pinfunction "1_1") (pintype "input"))
      (node (ref "D66") (pin "2") (pinfunction "2_2") (pintype "unspecified"))
    )
    (net (code "84") (name "Net-(68-Pad1)") (class "Default")
      (node (ref "68") (pin "1") (pinfunction "1_1") (pintype "input"))
      (node (ref "D68") (pin "2") (pinfunction "2_2") (pintype "unspecified"))
    )
    (net (code "85") (name "Net-(69-Pad1)") (class "Default")
      (node (ref "69") (pin "1") (pinfunction "1_1") (pintype "input"))
      (node (ref "D69") (pin "2") (pinfunction "2_2") (pintype "unspecified"))
    )
    (net (code "86") (name "Net-(70-Pad1)") (class "Default")
      (node (ref "70") (pin "1") (pinfunction "1_1") (pintype "input"))
      (node (ref "D70") (pin "2") (pinfunction "2_2") (pintype "unspecified"))
    )
    (net (code "87") (name "Net-(71-Pad1)") (class "Default")
      (node (ref "71") (pin "1") (pinfunction "1_1") (pintype "input"))
      (node (ref "D71") (pin "2") (pinfunction "2_2") (pintype "unspecified"))
    )
    (net (code "88") (name "Net-(73-Pad1)") (class "Default")
      (node (ref "73") (pin "1") (pinfunction "1_1") (pintype "input"))
      (node (ref "D73") (pin "2") (pinfunction "2_2") (pintype "unspecified"))
    )
    (net (code "89") (name "Net-(77-Pad1)") (class "Default")
      (node (ref "77") (pin "1") (pinfunction "1_1") (pintype "input"))
      (node (ref "D77") (pin "2") (pinfunction "2_2") (pintype "unspecified"))
    )
    (net (code "90") (name "Net-(81-Pad1)") (class "Default")
      (node (ref "81") (pin "1") (pinfunction "1_1") (pintype "input"))
      (node (ref "D81") (pin "2") (pinfunction "2_2") (pintype "unspecified"))
    )
    (net (code "91") (name "Net-(82-Pad1)") (class "Default")
      (node (ref "82") (pin "1") (pinfunction "1_1") (pintype "input"))
      (node (ref "D82") (pin "2") (pinfunction "2_2") (pintype "unspecified"))
    )
    (net (code "92") (name "Net-(84-Pad1)") (class "Default")
      (node (ref "84") (pin "1") (pinfunction "1_1") (pintype "input"))
      (node (ref "D84") (pin "2") (pinfunction "2_2") (pintype "unspecified"))
    )
    (net (code "93") (name "Net-(U1-D+)") (class "Default")
      (node (ref "R3") (pin "2") (pinfunction "2_2") (pintype "unspecified"))
      (node (ref "U1") (pin "4") (pinfunction "D+_4") (pintype "bidirectional"))
    )
    (net (code "94") (name "Net-(U1-D-)") (class "Default")
      (node (ref "R2") (pin "2") (pinfunction "2_2") (pintype "unspecified"))
      (node (ref "U1") (pin "3") (pinfunction "D-_3") (pintype "bidirectional"))
    )
    (net (code "95") (name "Net-(U1-PE2_(HWB#))") (class "Default")
      (node (ref "R1") (pin "1") (pinfunction "1_1") (pintype "unspecified"))
      (node (ref "U1") (pin "33") (pinfunction "PE2_(HWB#)_33") (pintype "bidirectional"))
    )
    (net (code "96") (name "Net-(U1-RESET#)") (class "Default")
      (node (ref "KEY1") (pin "2") (pinfunction "2_2") (pintype "unspecified"))
      (node (ref "R4") (pin "1") (pinfunction "1_1") (pintype "unspecified"))
      (node (ref "U1") (pin "13") (pinfunction "RESET#_13") (pintype "unspecified"))
    )
    (net (code "97") (name "Net-(U1-UCap)") (class "Default")
      (node (ref "C1") (pin "2") (pinfunction "2_2") (pintype "unspecified"))
      (node (ref "U1") (pin "6") (pinfunction "UCap_6") (pintype "unspecified"))
    )
    (net (code "98") (name "Net-(U1-XTAL1)") (class "Default")
      (node (ref "C7") (pin "2") (pinfunction "2_2") (pintype "unspecified"))
      (node (ref "U1") (pin "17") (pinfunction "XTAL1_17") (pintype "unspecified"))
      (node (ref "X1") (pin "1") (pinfunction "OSC1_1") (pintype "unspecified"))
    )
    (net (code "99") (name "Net-(U1-XTAL2)") (class "Default")
      (node (ref "C6") (pin "2") (pinfunction "2_2") (pintype "unspecified"))
      (node (ref "U1") (pin "16") (pinfunction "XTAL2_16") (pintype "output"))
      (node (ref "X1") (pin "3") (pinfunction "OSC2_3") (pintype "unspecified"))
    )
    (net (code "100") (name "Row0") (class "Default")
      (node (ref "D0") (pin "1") (pinfunction "1_1") (pintype "unspecified"))
      (node (ref "D1") (pin "1") (pinfunction "1_1") (pintype "unspecified"))
      (node (ref "D10") (pin "1") (pinfunction "1_1") (pintype "unspecified"))
      (node (ref "D11") (pin "1") (pinfunction "1_1") (pintype "unspecified"))
      (node (ref "D12") (pin "1") (pinfunction "1_1") (pintype "unspecified"))
      (node (ref "D13") (pin "1") (pinfunction "1_1") (pintype "unspecified"))
      (node (ref "D14") (pin "1") (pinfunction "1_1") (pintype "unspecified"))
      (node (ref "D15") (pin "1") (pinfunction "1_1") (pintype "unspecified"))
      (node (ref "D16") (pin "1") (pinfunction "1_1") (pintype "unspecified"))
      (node (ref "D2") (pin "1") (pinfunction "1_1") (pintype "unspecified"))
      (node (ref "D3") (pin "1") (pinfunction "1_1") (pintype "unspecified"))
      (node (ref "D4") (pin "1") (pinfunction "1_1") (pintype "unspecified"))
      (node (ref "D5") (pin "1") (pinfunction "1_1") (pintype "unspecified"))
      (node (ref "D6") (pin "1") (pinfunction "1_1") (pintype "unspecified"))
      (node (ref "D7") (pin "1") (pinfunction "1_1") (pintype "unspecified"))
      (node (ref "D8") (pin "1") (pinfunction "1_1") (pintype "unspecified"))
      (node (ref "D9") (pin "1") (pinfunction "1_1") (pintype "unspecified"))
      (node (ref "U1") (pin "38") (pinfunction "PF5_(ADC5/TMS))_38") (pintype "bidirectional"))
    )
    (net (code "101") (name "Row1") (class "Default")
      (node (ref "D17") (pin "1") (pinfunction "1_1") (pintype "unspecified"))
      (node (ref "D18") (pin "1") (pinfunction "1_1") (pintype "unspecified"))
      (node (ref "D19") (pin "1") (pinfunction "1_1") (pintype "unspecified"))
      (node (ref "D20") (pin "1") (pinfunction "1_1") (pintype "unspecified"))
      (node (ref "D21") (pin "1") (pinfunction "1_1") (pintype "unspecified"))
      (node (ref "D22") (pin "1") (pinfunction "1_1") (pintype "unspecified"))
      (node (ref "D23") (pin "1") (pinfunction "1_1") (pintype "unspecified"))
      (node (ref "D24") (pin "1") (pinfunction "1_1") (pintype "unspecified"))
      (node (ref "D25") (pin "1") (pinfunction "1_1") (pintype "unspecified"))
      (node (ref "D26") (pin "1") (pinfunction "1_1") (pintype "unspecified"))
      (node (ref "D27") (pin "1") (pinfunction "1_1") (pintype "unspecified"))
      (node (ref "D28") (pin "1") (pinfunction "1_1") (pintype "unspecified"))
      (node (ref "D29") (pin "1") (pinfunction "1_1") (pintype "unspecified"))
      (node (ref "D30") (pin "1") (pinfunction "1_1") (pintype "unspecified"))
      (node (ref "D31") (pin "1") (pinfunction "1_1") (pintype "unspecified"))
      (node (ref "D33") (pin "1") (pinfunction "1_1") (pintype "unspecified"))
      (node (ref "U1") (pin "39") (pinfunction "PF4_(ADC4/TCK)_39") (pintype "bidirectional"))
    )
    (net (code "102") (name "Row2") (class "Default")
      (node (ref "D34") (pin "1") (pinfunction "1_1") (pintype "unspecified"))
      (node (ref "D36") (pin "1") (pinfunction "1_1") (pintype "unspecified"))
      (node (ref "D37") (pin "1") (pinfunction "1_1") (pintype "unspecified"))
      (node (ref "D38") (pin "1") (pinfunction "1_1") (pintype "unspecified"))
      (node (ref "D39") (pin "1") (pinfunction "1_1") (pintype "unspecified"))
      (node (ref "D40") (pin "1") (pinfunction "1_1") (pintype "unspecified"))
      (node (ref "D41") (pin "1") (pinfunction "1_1") (pintype "unspecified"))
      (node (ref "D42") (pin "1") (pinfunction "1_1") (pintype "unspecified"))
      (node (ref "D43") (pin "1") (pinfunction "1_1") (pintype "unspecified"))
      (node (ref "D44") (pin "1") (pinfunction "1_1") (pintype "unspecified"))
      (node (ref "D45") (pin "1") (pinfunction "1_1") (pintype "unspecified"))
      (node (ref "D46") (pin "1") (pinfunction "1_1") (pintype "unspecified"))
      (node (ref "D47") (pin "1") (pinfunction "1_1") (pintype "unspecified"))
      (node (ref "D49") (pin "1") (pinfunction "1_1") (pintype "unspecified"))
      (node (ref "D50") (pin "1") (pinfunction "1_1") (pintype "unspecified"))
      (node (ref "U1") (pin "40") (pinfunction "PF1_(ADC1)_40") (pintype "bidirectional"))
    )
    (net (code "103") (name "Row3") (class "Default")
      (node (ref "D52") (pin "1") (pinfunction "1_1") (pintype "unspecified"))
      (node (ref "D53") (pin "1") (pinfunction "1_1") (pintype "unspecified"))
      (node (ref "D54") (pin "1") (pinfunction "1_1") (pintype "unspecified"))
      (node (ref "D55") (pin "1") (pinfunction "1_1") (pintype "unspecified"))
      (node (ref "D56") (pin "1") (pinfunction "1_1") (pintype "unspecified"))
      (node (ref "D57") (pin "1") (pinfunction "1_1") (pintype "unspecified"))
      (node (ref "D58") (pin "1") (pinfunction "1_1") (pintype "unspecified"))
      (node (ref "D59") (pin "1") (pinfunction "1_1") (pintype "unspecified"))
      (node (ref "D60") (pin "1") (pinfunction "1_1") (pintype "unspecified"))
      (node (ref "D61") (pin "1") (pinfunction "1_1") (pintype "unspecified"))
      (node (ref "D62") (pin "1") (pinfunction "1_1") (pintype "unspecified"))
      (node (ref "D64") (pin "1") (pinfunction "1_1") (pintype "unspecified"))
      (node (ref "D65") (pin "1") (pinfunction "1_1") (pintype "unspecified"))
      (node (ref "D66") (pin "1") (pinfunction "1_1") (pintype "unspecified"))
      (node (ref "U1") (pin "41") (pinfunction "PF0_(ADC0)_41") (pintype "bidirectional"))
    )
    (net (code "104") (name "Row4") (class "Default")
      (node (ref "D68") (pin "1") (pinfunction "1_1") (pintype "unspecified"))
      (node (ref "D69") (pin "1") (pinfunction "1_1") (pintype "unspecified"))
      (node (ref "D70") (pin "1") (pinfunction "1_1") (pintype "unspecified"))
      (node (ref "D71") (pin "1") (pinfunction "1_1") (pintype "unspecified"))
      (node (ref "D73") (pin "1") (pinfunction "1_1") (pintype "unspecified"))
      (node (ref "D77") (pin "1") (pinfunction "1_1") (pintype "unspecified"))
      (node (ref "D81") (pin "1") (pinfunction "1_1") (pintype "unspecified"))
      (node (ref "D82") (pin "1") (pinfunction "1_1") (pintype "unspecified"))
      (node (ref "D84") (pin "1") (pinfunction "1_1") (pintype "unspecified"))
      (node (ref "U1") (pin "1") (pinfunction "PE6_(INT.6/AIN0)_1") (pintype "bidirectional"))
    )
    (net (code "105") (name "VCC") (class "Default")
      (node (ref "F1") (pin "1") (pinfunction "1_1") (pintype "unspecified"))
      (node (ref "USB1") (pin "1") (pinfunction "VBUS_1") (pintype "unspecified"))
    )
    (net (code "106") (name "unconnected-(U1-AREF-Pad42)") (class "Default")
      (node (ref "U1") (pin "42") (pinfunction "AREF_42") (pintype "unspecified"))
    )
    (net (code "107") (name "unconnected-(U1-PB0(SS{slash}PCINT0)-Pad8)") (class "Default")
      (node (ref "U1") (pin "8") (pinfunction "PB0(SS/PCINT0)_8") (pintype "bidirectional"))
    )
    (net (code "108") (name "unconnected-(U1-PB7(PCINT7{slash}OC0A{slash}OC1C{slash}RTS#)-Pad12)") (class "Default")
      (node (ref "U1") (pin "12") (pinfunction "PB7(PCINT7/OC0A/OC1C/RTS#)_12") (pintype "bidirectional"))
    )
    (net (code "109") (name "unconnected-(U1-PD4(ICP1{slash}ADC8)-Pad25)") (class "Default")
      (node (ref "U1") (pin "25") (pinfunction "PD4(ICP1/ADC8)_25") (pintype "bidirectional"))
    )
    (net (code "110") (name "unconnected-(USB1-ID-Pad4)") (class "Default")
      (node (ref "USB1") (pin "4") (pinfunction "ID_4") (pintype "unspecified"))
    )
  )
)
